# DebugConsole.net
KiCad netlist of a schematic drawn in Altium Designer
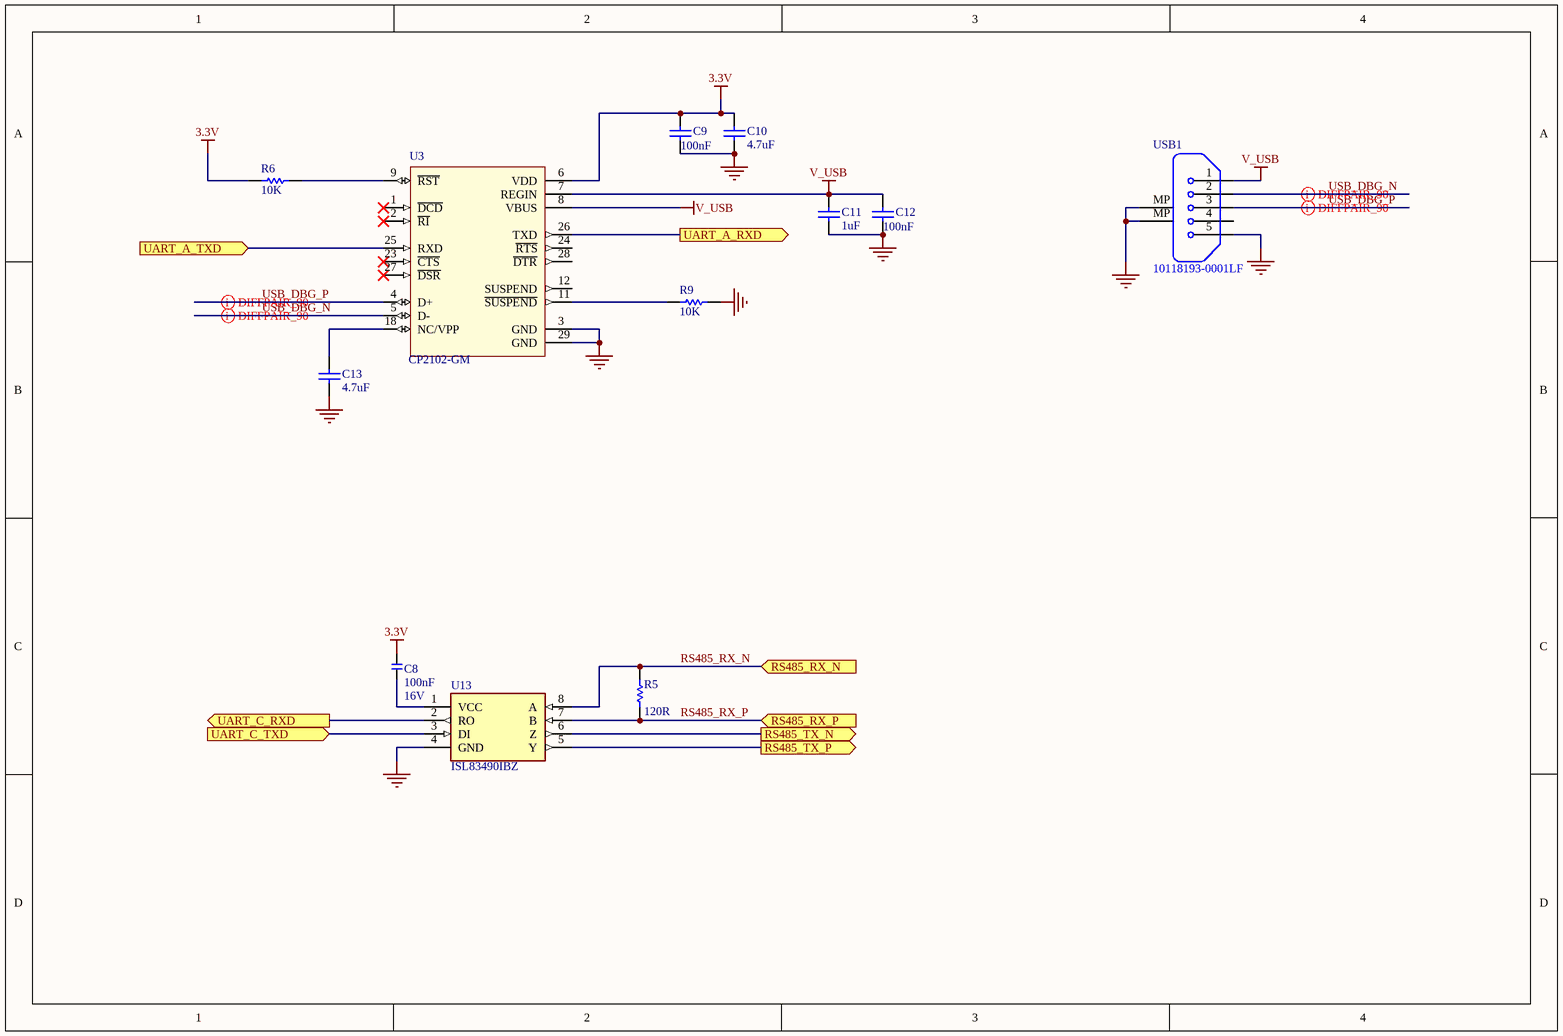
[diagram p0: DebugConsole.SchDoc]

(export (version "E")
  (design (tool "Eeschema 10.0.6"))
  (components
    (comp (ref "C8")
      (value "100nF")
      (footprint "T_CAPC0603X33N")
      (description "Capacitor Ceramic X7R 100nF 16V 10% 0603")
      (fields (field (name "TOLERANCE") "10%") (field (name "RATING") "16V"))
      (libsource (lib "Iris") (part "C-X7R-100nF-16V-10%-0603"))
    )
    (comp (ref "C9")
      (value "100nF")
      (footprint "CAPC1608X06L")
      (description "Capacitor")
      (fields (field (name "MPN") "MC0603B104K250CT") (field (name "PUBLISHER") "Altium Limited"))
      (libsource (lib "Miscellaneous Devices") (part "Cap"))
    )
    (comp (ref "C10")
      (value "4.7uF")
      (footprint "CAPC1608X100N")
      (fields (field (name "MPN") "C0603C475K9PACTU"))
      (libsource (lib "Passive components") (part "CAP"))
    )
    (comp (ref "C11")
      (value "1uF")
      (footprint "CAPC1608X100N")
      (fields (field (name "MPN") "C0603C105K8PACTU"))
      (libsource (lib "Passive components") (part "CAP"))
    )
    (comp (ref "C12")
      (value "100nF")
      (footprint "CAPC1608X06L")
      (description "Capacitor")
      (fields (field (name "MPN") "MC0603B104K250CT") (field (name "PUBLISHER") "Altium Limited"))
      (libsource (lib "Miscellaneous Devices") (part "Cap"))
    )
    (comp (ref "C13")
      (value "4.7uF")
      (footprint "CAPC1608X100N")
      (fields (field (name "MPN") "C0603C475K9PACTU"))
      (libsource (lib "Passive components") (part "CAP"))
    )
    (comp (ref "R5")
      (value "120R")
      (footprint "T_RESC0603X30N")
      (description "Resistor")
      (fields (field (name "PUBLISHER") "Altium Limited"))
      (libsource (lib "Miscellaneous Devices") (part "Res1"))
    )
    (comp (ref "R6")
      (value "10K")
      (footprint "RESC1608X50N")
      (description "Resistor")
      (fields (field (name "MPN") "CRCW060310K0FKEAHP"))
      (libsource (lib "Miscellaneous Devices") (part "Res1"))
    )
    (comp (ref "R9")
      (value "10K")
      (footprint "RESC1608X50N")
      (description "Resistor")
      (fields (field (name "MPN") "CRCW060310K0FKEAHP"))
      (libsource (lib "Miscellaneous Devices") (part "Res1"))
    )
    (comp (ref "U3")
      (value "CP2102-GM")
      (footprint "QFN50P500X500X100-29N")
      (description "USB Bridge, USB to UART USB 2.0 UART Interface 28-QFN (5x5)")
      (fields (field (name "MF") "Silicon Labs"))
      (libsource (lib "CP2102-GM") (part "CP2102-GM"))
    )
    (comp (ref "U13")
      (value "ISL83490IBZ")
      (footprint "SOIC127P600X175-8N")
      (description "1/1 Transceiver Full RS422, RS485 8-SOIC")
      (fields
        (field (name "DIGI-KEY_PART_NUMBER") "ISL83490IBZ-TTR-ND")
        (field (name "MF") "Renesas / Intersil")
      )
      (libsource (lib "Schlib1") (part "ISL83490IBZ"))
    )
    (comp (ref "USB1")
      (value "10118193-0001LF")
      (footprint "10118193-0001LF")
      (libsource (lib "ESP32") (part "USB Micro-B"))
    )
  )
  (nets
    (net (code "1") (name "/RS485_RX_N") (class "Default")
      (node (ref "R5") (pin "2") (pinfunction "2_2") (pintype "passive"))
      (node (ref "U13") (pin "8") (pinfunction "A_8") (pintype "input"))
    )
    (net (code "2") (name "/RS485_RX_P") (class "Default")
      (node (ref "R5") (pin "1") (pinfunction "1_1") (pintype "passive"))
      (node (ref "U13") (pin "7") (pinfunction "B_7") (pintype "input"))
    )
    (net (code "3") (name "/RS485_TX_N") (class "Default")
      (node (ref "U13") (pin "6") (pinfunction "Z_6") (pintype "output"))
    )
    (net (code "4") (name "/RS485_TX_P") (class "Default")
      (node (ref "U13") (pin "5") (pinfunction "Y_5") (pintype "output"))
    )
    (net (code "5") (name "/UART_A_RXD") (class "Default")
      (node (ref "U3") (pin "26") (pinfunction "TXD_26") (pintype "output"))
    )
    (net (code "6") (name "/UART_A_TXD") (class "Default")
      (node (ref "U3") (pin "25") (pinfunction "RXD_25") (pintype "input"))
    )
    (net (code "7") (name "/UART_C_RXD") (class "Default")
      (node (ref "U13") (pin "2") (pinfunction "RO_2") (pintype "output"))
    )
    (net (code "8") (name "/UART_C_TXD") (class "Default")
      (node (ref "U13") (pin "3") (pinfunction "DI_3") (pintype "input"))
    )
    (net (code "9") (name "/USB_DBG_N") (class "Default")
      (node (ref "U3") (pin "5") (pinfunction "D-_5") (pintype "bidirectional"))
      (node (ref "USB1") (pin "2") (pinfunction "2_2") (pintype "passive"))
    )
    (net (code "10") (name "/USB_DBG_P") (class "Default")
      (node (ref "U3") (pin "4") (pinfunction "D+_4") (pintype "bidirectional"))
      (node (ref "USB1") (pin "3") (pinfunction "3_3") (pintype "passive"))
    )
    (net (code "11") (name "3.3V") (class "Default")
      (node (ref "C10") (pin "1") (pinfunction "1_1") (pintype "passive"))
      (node (ref "C8") (pin "2") (pinfunction "2_2") (pintype "passive"))
      (node (ref "C9") (pin "1") (pinfunction "1_1") (pintype "passive"))
      (node (ref "R6") (pin "1") (pinfunction "1_1") (pintype "passive"))
      (node (ref "U3") (pin "6") (pinfunction "VDD_6") (pintype "power_in"))
    )
    (net (code "12") (name "GND") (class "Default")
      (node (ref "C10") (pin "2") (pinfunction "2_2") (pintype "passive"))
      (node (ref "C11") (pin "2") (pinfunction "2_2") (pintype "passive"))
      (node (ref "C12") (pin "2") (pinfunction "2_2") (pintype "passive"))
      (node (ref "C13") (pin "2") (pinfunction "2_2") (pintype "passive"))
      (node (ref "C9") (pin "2") (pinfunction "2_2") (pintype "passive"))
      (node (ref "R9") (pin "2") (pinfunction "2_2") (pintype "passive"))
      (node (ref "U13") (pin "4") (pinfunction "GND_4") (pintype "power_in"))
      (node (ref "U3") (pin "29") (pinfunction "GND_29") (pintype "power_in"))
      (node (ref "U3") (pin "3") (pinfunction "GND_3") (pintype "power_in"))
      (node (ref "USB1") (pin "5") (pinfunction "5_5") (pintype "passive"))
      (node (ref "USB1") (pin "6") (pinfunction "6_6") (pintype "passive"))
    )
    (net (code "13") (name "Net-(U3-NC{slash}VPP)") (class "Default")
      (node (ref "C13") (pin "1") (pinfunction "1_1") (pintype "passive"))
      (node (ref "U3") (pin "18") (pinfunction "NC/VPP_18") (pintype "bidirectional"))
    )
    (net (code "14") (name "Net-(U3-~{RST})") (class "Default")
      (node (ref "R6") (pin "2") (pinfunction "2_2") (pintype "passive"))
      (node (ref "U3") (pin "9") (pinfunction "~{RST}_9") (pintype "bidirectional"))
    )
    (net (code "15") (name "Net-(U3-~{SUSPEND})") (class "Default")
      (node (ref "R9") (pin "1") (pinfunction "1_1") (pintype "passive"))
      (node (ref "U3") (pin "11") (pinfunction "~{SUSPEND}_11") (pintype "output"))
    )
    (net (code "16") (name "Net-(U13-VCC)") (class "Default")
      (node (ref "C8") (pin "1") (pinfunction "1_1") (pintype "passive"))
      (node (ref "U13") (pin "1") (pinfunction "VCC_1") (pintype "power_in"))
    )
    (net (code "17") (name "V_USB") (class "Default")
      (node (ref "C11") (pin "1") (pinfunction "1_1") (pintype "passive"))
      (node (ref "C12") (pin "1") (pinfunction "1_1") (pintype "passive"))
      (node (ref "U3") (pin "7") (pinfunction "REGIN_7") (pintype "power_in"))
      (node (ref "U3") (pin "8") (pinfunction "VBUS_8") (pintype "power_in"))
      (node (ref "USB1") (pin "1") (pinfunction "1_1") (pintype "passive"))
    )
    (net (code "18") (name "unconnected-(U3-SUSPEND-Pad12)") (class "Default")
      (node (ref "U3") (pin "12") (pinfunction "SUSPEND_12") (pintype "output"))
    )
    (net (code "19") (name "unconnected-(U3-~{CTS}-Pad23)") (class "Default")
      (node (ref "U3") (pin "23") (pinfunction "~{CTS}_23") (pintype "input+no_connect"))
    )
    (net (code "20") (name "unconnected-(U3-~{DCD}-Pad1)") (class "Default")
      (node (ref "U3") (pin "1") (pinfunction "~{DCD}_1") (pintype "input+no_connect"))
    )
    (net (code "21") (name "unconnected-(U3-~{DSR}-Pad27)") (class "Default")
      (node (ref "U3") (pin "27") (pinfunction "~{DSR}_27") (pintype "input+no_connect"))
    )
    (net (code "22") (name "unconnected-(U3-~{DTR}-Pad28)") (class "Default")
      (node (ref "U3") (pin "28") (pinfunction "~{DTR}_28") (pintype "output"))
    )
    (net (code "23") (name "unconnected-(U3-~{RI}-Pad2)") (class "Default")
      (node (ref "U3") (pin "2") (pinfunction "~{RI}_2") (pintype "input+no_connect"))
    )
    (net (code "24") (name "unconnected-(U3-~{RTS}-Pad24)") (class "Default")
      (node (ref "U3") (pin "24") (pinfunction "~{RTS}_24") (pintype "output"))
    )
    (net (code "25") (name "unconnected-(USB1-Pad4)") (class "Default")
      (node (ref "USB1") (pin "4") (pinfunction "4_4") (pintype "passive"))
    )
  )
)
